# Cherry.net
KiCad netlist of a schematic drawn in Altium Designer
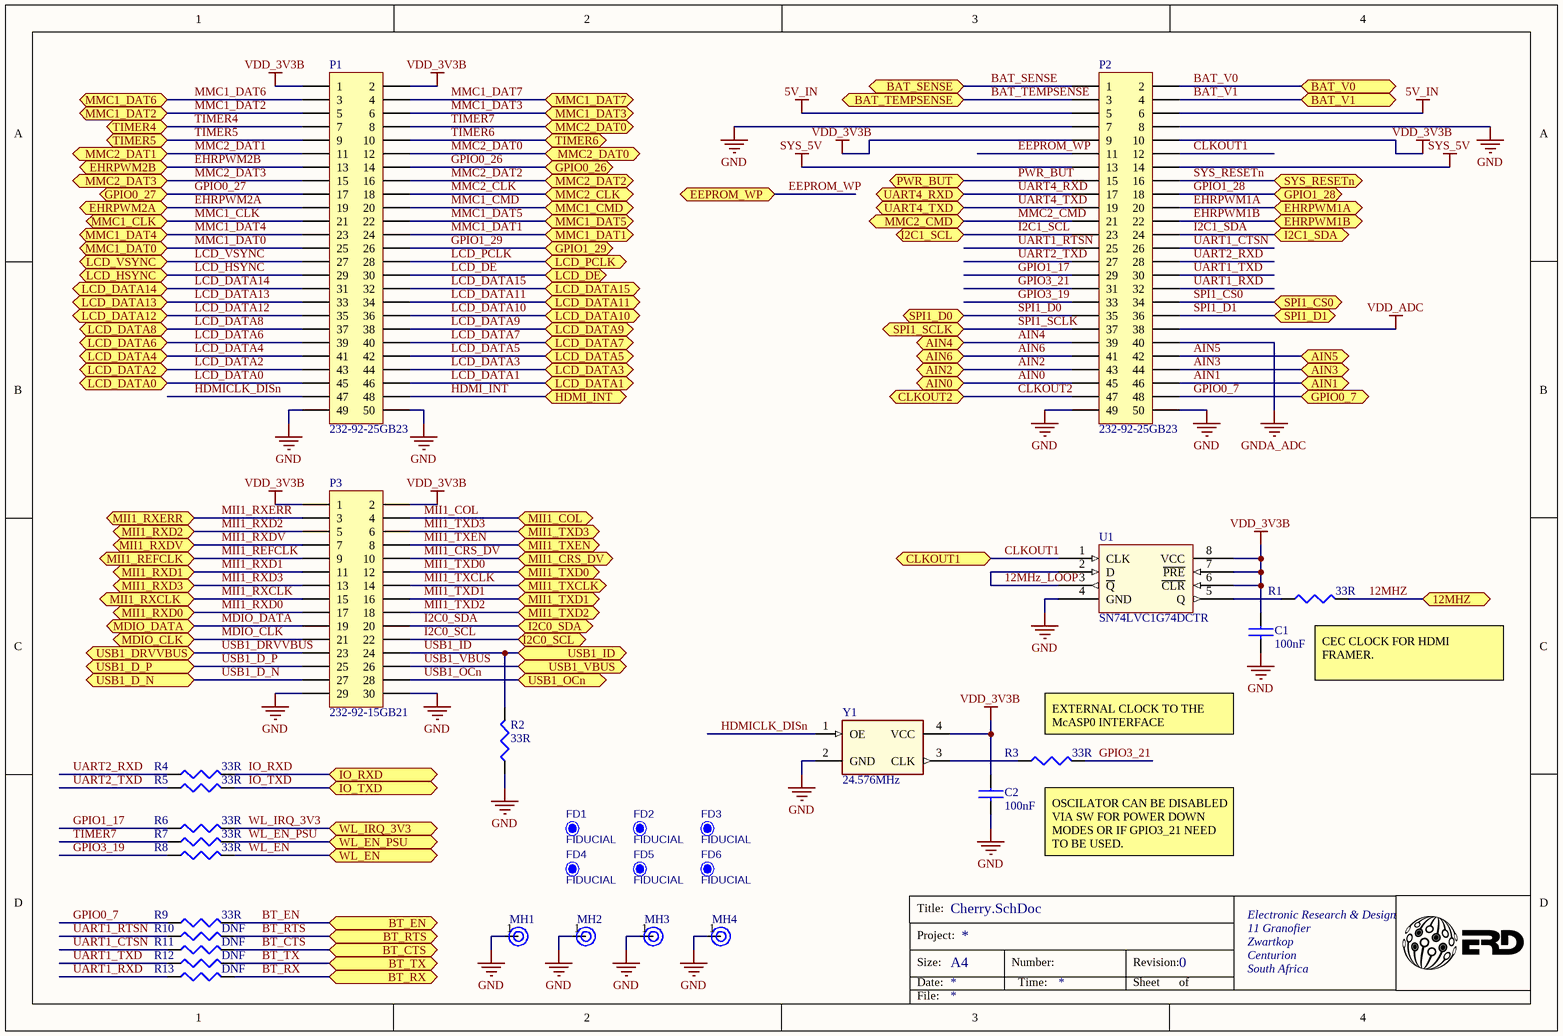
[diagram p0: Cherry.SchDoc]

(export (version "E")
  (design (tool "Eeschema 10.0.6"))
  (components
    (comp (ref "C1")
      (value "100nF")
      (footprint "CC0402")
      (description "CAP CER 0.1UF 50V 10% X7R 0402")
      (fields (field (name "MANUFACTURER") "Murata") (field (name "PARTNUMBER") "GCM155R71H104KE02D"))
      (libsource (lib "ERD TiAm") (part "CAP CER 0.1UF 10V 10% X5R 0402"))
    )
    (comp (ref "C2")
      (value "100nF")
      (footprint "CC0402")
      (description "CAP CER 0.1UF 50V 10% X7R 0402")
      (fields (field (name "MANUFACTURER") "Murata") (field (name "PARTNUMBER") "GCM155R71H104KE02D"))
      (libsource (lib "ERD TiAm") (part "CAP CER 0.1UF 10V 10% X5R 0402"))
    )
    (comp (ref "FD1")
      (value "FIDUCIAL")
      (footprint "FIDUCIAL")
      (description "Fiducial 2mm")
      (libsource (lib "*") (part "FIDUCIAL"))
    )
    (comp (ref "FD2")
      (value "FIDUCIAL")
      (footprint "FIDUCIAL")
      (description "Fiducial 2mm")
      (libsource (lib "*") (part "FIDUCIAL"))
    )
    (comp (ref "FD3")
      (value "FIDUCIAL")
      (footprint "FIDUCIAL")
      (description "Fiducial 2mm")
      (libsource (lib "*") (part "FIDUCIAL"))
    )
    (comp (ref "FD4")
      (value "FIDUCIAL")
      (footprint "FIDUCIAL")
      (description "Fiducial 2mm")
      (libsource (lib "*") (part "FIDUCIAL"))
    )
    (comp (ref "FD5")
      (value "FIDUCIAL")
      (footprint "FIDUCIAL")
      (description "Fiducial 2mm")
      (libsource (lib "*") (part "FIDUCIAL"))
    )
    (comp (ref "FD6")
      (value "FIDUCIAL")
      (footprint "FIDUCIAL")
      (description "Fiducial 2mm")
      (libsource (lib "*") (part "FIDUCIAL"))
    )
    (comp (ref "MH1")
      (value "MH")
      (footprint "MH - M3")
      (description "Mounting Hole")
      (libsource (lib "BCI_rev_0") (part "MountingHole"))
    )
    (comp (ref "MH2")
      (value "MH")
      (footprint "MH - M3")
      (description "Mounting Hole")
      (libsource (lib "BCI_rev_0") (part "MountingHole"))
    )
    (comp (ref "MH3")
      (value "MH")
      (footprint "MH - M3")
      (description "Mounting Hole")
      (libsource (lib "BCI_rev_0") (part "MountingHole"))
    )
    (comp (ref "MH4")
      (value "MH")
      (footprint "MH - M3")
      (description "Mounting Hole")
      (libsource (lib "BCI_rev_0") (part "MountingHole"))
    )
    (comp (ref "P1")
      (value "232-92-25GB23")
      (footprint "232-92-25GB")
      (description "Header, 25-Pin Male, Dual row")
      (fields
        (field (name "MANUFACTURER") "Pinrex")
        (field (name "MANUFACTURER PART NUMBER") "635-92-25GB02")
      )
      (libsource (lib "ERD TiAm") (part "Header 25X2"))
    )
    (comp (ref "P2")
      (value "232-92-25GB23")
      (footprint "232-92-25GB")
      (description "Header, 25-Pin Male, Dual row")
      (fields
        (field (name "MANUFACTURER") "Pinrex")
        (field (name "MANUFACTURER PART NUMBER") "635-92-25GB02")
      )
      (libsource (lib "ERD TiAm") (part "Header 25X2"))
    )
    (comp (ref "P3")
      (value "232-92-15GB21")
      (footprint "232-92-15GB")
      (description "Header, 15-Pin Male, Dual row")
      (fields
        (field (name "MANUFACTURER") "Pinrex")
        (field (name "MANUFACTURER PART NUMBER") "635-92-15GB02")
      )
      (libsource (lib "ERD TiAm") (part "Header 15X2"))
    )
    (comp (ref "R1")
      (value "33R")
      (footprint "RC0402")
      (description "RES, 33 OHM, 1/16W, 1%, 0402")
      (fields (field (name "MANUFACTURER") "Yageo") (field (name "PARTNUMBER") "RC0402FR-0733RL"))
      (libsource (lib "ERD TiAm") (part "RES_10K_1/16W_1%_0402"))
    )
    (comp (ref "R2")
      (value "33R")
      (footprint "RC0402")
      (description "RES, 33 OHM, 1/16W, 1%, 0402")
      (fields (field (name "MANUFACTURER") "Yageo") (field (name "PARTNUMBER") "RC0402FR-0733RL"))
      (libsource (lib "ERD TiAm") (part "RES_10K_1/16W_1%_0402"))
    )
    (comp (ref "R3")
      (value "33R")
      (footprint "RC0402")
      (description "RES, 33 OHM, 1/16W, 1%, 0402")
      (fields (field (name "MANUFACTURER") "Yageo") (field (name "PARTNUMBER") "RC0402FR-0733RL"))
      (libsource (lib "ERD TiAm") (part "RES_10K_1/16W_1%_0402"))
    )
    (comp (ref "R4")
      (value "33R")
      (footprint "RC0402")
      (description "RES, 33 OHM, 1/16W, 1%, 0402")
      (fields (field (name "MANUFACTURER") "Yageo") (field (name "PARTNUMBER") "RC0402FR-0733RL"))
      (libsource (lib "ERD TiAm") (part "RES_10K_1/16W_1%_0402"))
    )
    (comp (ref "R5")
      (value "33R")
      (footprint "RC0402")
      (description "RES, 33 OHM, 1/16W, 1%, 0402")
      (fields (field (name "MANUFACTURER") "Yageo") (field (name "PARTNUMBER") "RC0402FR-0733RL"))
      (libsource (lib "ERD TiAm") (part "RES_10K_1/16W_1%_0402"))
    )
    (comp (ref "R6")
      (value "33R")
      (footprint "RC0402")
      (description "RES, 33 OHM, 1/16W, 1%, 0402")
      (fields (field (name "MANUFACTURER") "Yageo") (field (name "PARTNUMBER") "RC0402FR-0733RL"))
      (libsource (lib "ERD TiAm") (part "RES_10K_1/16W_1%_0402"))
    )
    (comp (ref "R7")
      (value "33R")
      (footprint "RC0402")
      (description "RES, 33 OHM, 1/16W, 1%, 0402")
      (fields (field (name "MANUFACTURER") "Yageo") (field (name "PARTNUMBER") "RC0402FR-0733RL"))
      (libsource (lib "ERD TiAm") (part "RES_10K_1/16W_1%_0402"))
    )
    (comp (ref "R8")
      (value "33R")
      (footprint "RC0402")
      (description "RES, 33 OHM, 1/16W, 1%, 0402")
      (fields (field (name "MANUFACTURER") "Yageo") (field (name "PARTNUMBER") "RC0402FR-0733RL"))
      (libsource (lib "ERD TiAm") (part "RES_10K_1/16W_1%_0402"))
    )
    (comp (ref "R9")
      (value "33R")
      (footprint "RC0402")
      (description "RES, 33 OHM, 1/16W, 1%, 0402")
      (fields (field (name "MANUFACTURER") "Yageo") (field (name "PARTNUMBER") "RC0402FR-0733RL"))
      (libsource (lib "ERD TiAm") (part "RES_10K_1/16W_1%_0402"))
    )
    (comp (ref "R10")
      (value "DNF")
      (footprint "RC0402")
      (description "RES, 33 OHM, 1/16W, 1%, 0402")
      (fields (field (name "MANUFACTURER") "Yageo") (field (name "PARTNUMBER") "RC0402FR-0733RL"))
      (libsource (lib "ERD TiAm") (part "RES_10K_1/16W_1%_0402"))
    )
    (comp (ref "R11")
      (value "DNF")
      (footprint "RC0402")
      (description "RES, 33 OHM, 1/16W, 1%, 0402")
      (fields (field (name "MANUFACTURER") "Yageo") (field (name "PARTNUMBER") "RC0402FR-0733RL"))
      (libsource (lib "ERD TiAm") (part "RES_10K_1/16W_1%_0402"))
    )
    (comp (ref "R12")
      (value "DNF")
      (footprint "RC0402")
      (description "RES, 33 OHM, 1/16W, 1%, 0402")
      (fields (field (name "MANUFACTURER") "Yageo") (field (name "PARTNUMBER") "RC0402FR-0733RL"))
      (libsource (lib "ERD TiAm") (part "RES_10K_1/16W_1%_0402"))
    )
    (comp (ref "R13")
      (value "DNF")
      (footprint "RC0402")
      (description "RES, 33 OHM, 1/16W, 1%, 0402")
      (fields (field (name "MANUFACTURER") "Yageo") (field (name "PARTNUMBER") "RC0402FR-0733RL"))
      (libsource (lib "ERD TiAm") (part "RES_10K_1/16W_1%_0402"))
    )
    (comp (ref "U1")
      (value "SN74LVC1G74DCTR")
      (footprint "SOP8_DCT")
      (description "SINGLE  POSITIVE-EDGE-TRIGGERED  D-TYPE  FLIP-FLOP WITH  CLEAR  AND  PRESET")
      (fields (field (name "MANUFACTURER") "Texas Instruments"))
      (libsource (lib "BEAGLEBONEBLACK_REV A5B") (part "SN74LVC1G74DCTR"))
    )
    (comp (ref "Y1")
      (value "24.576MHz")
      (footprint "OSC_SMD_7x5")
      (fields
        (field (name "MANUFACTURER") "Abracon Corporation")
        (field (name "MANUFACTURER PART NUMBER") "ASDMB-24.576MHZ-LC-T")
      )
      (libsource (lib "BEAGLEBONEBLACK_REV A5B") (part "ASDMB"))
    )
  )
  (nets
    (net (code "1") (name "/12MHZ") (class "Default")
      (node (ref "R1") (pin "2") (pinfunction "2_2") (pintype "passive"))
    )
    (net (code "2") (name "/12MHz_LOOP") (class "Default")
      (node (ref "U1") (pin "2") (pinfunction "D_2") (pintype "input"))
      (node (ref "U1") (pin "3") (pinfunction "~{Q}_3") (pintype "output"))
    )
    (net (code "3") (name "/AIN0") (class "Default")
      (node (ref "P2") (pin "45") (pinfunction "45_45") (pintype "passive"))
    )
    (net (code "4") (name "/AIN1") (class "Default")
      (node (ref "P2") (pin "46") (pinfunction "46_46") (pintype "passive"))
    )
    (net (code "5") (name "/AIN2") (class "Default")
      (node (ref "P2") (pin "43") (pinfunction "43_43") (pintype "passive"))
    )
    (net (code "6") (name "/AIN3") (class "Default")
      (node (ref "P2") (pin "44") (pinfunction "44_44") (pintype "passive"))
    )
    (net (code "7") (name "/AIN4") (class "Default")
      (node (ref "P2") (pin "39") (pinfunction "39_39") (pintype "passive"))
    )
    (net (code "8") (name "/AIN5") (class "Default")
      (node (ref "P2") (pin "42") (pinfunction "42_42") (pintype "passive"))
    )
    (net (code "9") (name "/AIN6") (class "Default")
      (node (ref "P2") (pin "41") (pinfunction "41_41") (pintype "passive"))
    )
    (net (code "10") (name "/BAT_SENSE") (class "Default")
      (node (ref "P2") (pin "1") (pinfunction "1_1") (pintype "passive"))
    )
    (net (code "11") (name "/BAT_TEMPSENSE") (class "Default")
      (node (ref "P2") (pin "3") (pinfunction "3_3") (pintype "passive"))
    )
    (net (code "12") (name "/BAT_V0") (class "Default")
      (node (ref "P2") (pin "2") (pinfunction "2_2") (pintype "passive"))
    )
    (net (code "13") (name "/BAT_V1") (class "Default")
      (node (ref "P2") (pin "4") (pinfunction "4_4") (pintype "passive"))
    )
    (net (code "14") (name "/BT_CTS") (class "Default")
      (node (ref "R11") (pin "2") (pinfunction "2_2") (pintype "passive"))
    )
    (net (code "15") (name "/BT_EN") (class "Default")
      (node (ref "R9") (pin "2") (pinfunction "2_2") (pintype "passive"))
    )
    (net (code "16") (name "/BT_RTS") (class "Default")
      (node (ref "R10") (pin "2") (pinfunction "2_2") (pintype "passive"))
    )
    (net (code "17") (name "/BT_RX") (class "Default")
      (node (ref "R13") (pin "2") (pinfunction "2_2") (pintype "passive"))
    )
    (net (code "18") (name "/BT_TX") (class "Default")
      (node (ref "R12") (pin "2") (pinfunction "2_2") (pintype "passive"))
    )
    (net (code "19") (name "/CLKOUT1") (class "Default")
      (node (ref "P2") (pin "12") (pinfunction "12_12") (pintype "passive"))
      (node (ref "U1") (pin "1") (pinfunction "CLK_1") (pintype "input"))
    )
    (net (code "20") (name "/CLKOUT2") (class "Default")
      (node (ref "P2") (pin "47") (pinfunction "47_47") (pintype "passive"))
    )
    (net (code "21") (name "/EEPROM_WP") (class "Default")
      (node (ref "P2") (pin "11") (pinfunction "11_11") (pintype "passive"))
    )
    (net (code "22") (name "/EHRPWM1A") (class "Default")
      (node (ref "P2") (pin "20") (pinfunction "20_20") (pintype "passive"))
    )
    (net (code "23") (name "/EHRPWM1B") (class "Default")
      (node (ref "P2") (pin "22") (pinfunction "22_22") (pintype "passive"))
    )
    (net (code "24") (name "/EHRPWM2A") (class "Default")
      (node (ref "P1") (pin "19") (pinfunction "19_19") (pintype "passive"))
    )
    (net (code "25") (name "/EHRPWM2B") (class "Default")
      (node (ref "P1") (pin "13") (pinfunction "13_13") (pintype "passive"))
    )
    (net (code "26") (name "/GPIO0_7") (class "Default")
      (node (ref "P2") (pin "48") (pinfunction "48_48") (pintype "passive"))
      (node (ref "R9") (pin "1") (pinfunction "1_1") (pintype "passive"))
    )
    (net (code "27") (name "/GPIO0_26") (class "Default")
      (node (ref "P1") (pin "14") (pinfunction "14_14") (pintype "passive"))
    )
    (net (code "28") (name "/GPIO0_27") (class "Default")
      (node (ref "P1") (pin "17") (pinfunction "17_17") (pintype "passive"))
    )
    (net (code "29") (name "/GPIO1_17") (class "Default")
      (node (ref "P2") (pin "29") (pinfunction "29_29") (pintype "passive"))
      (node (ref "R6") (pin "1") (pinfunction "1_1") (pintype "passive"))
    )
    (net (code "30") (name "/GPIO1_28") (class "Default")
      (node (ref "P2") (pin "18") (pinfunction "18_18") (pintype "passive"))
    )
    (net (code "31") (name "/GPIO1_29") (class "Default")
      (node (ref "P1") (pin "26") (pinfunction "26_26") (pintype "passive"))
    )
    (net (code "32") (name "/GPIO3_19") (class "Default")
      (node (ref "P2") (pin "33") (pinfunction "33_33") (pintype "passive"))
      (node (ref "R8") (pin "1") (pinfunction "1_1") (pintype "passive"))
    )
    (net (code "33") (name "/GPIO3_21") (class "Default")
      (node (ref "P2") (pin "31") (pinfunction "31_31") (pintype "passive"))
      (node (ref "R3") (pin "2") (pinfunction "2_2") (pintype "passive"))
    )
    (net (code "34") (name "/HDMICLK_DISn") (class "Default")
      (node (ref "P1") (pin "47") (pinfunction "47_47") (pintype "passive"))
      (node (ref "Y1") (pin "1") (pinfunction "OE_1") (pintype "input"))
    )
    (net (code "35") (name "/HDMI_INT") (class "Default")
      (node (ref "P1") (pin "48") (pinfunction "48_48") (pintype "passive"))
    )
    (net (code "36") (name "/I2C0_SCL") (class "Default")
      (node (ref "P3") (pin "22") (pinfunction "22_22") (pintype "passive"))
    )
    (net (code "37") (name "/I2C0_SDA") (class "Default")
      (node (ref "P3") (pin "20") (pinfunction "20_20") (pintype "passive"))
    )
    (net (code "38") (name "/I2C1_SCL") (class "Default")
      (node (ref "P2") (pin "23") (pinfunction "23_23") (pintype "passive"))
    )
    (net (code "39") (name "/I2C1_SDA") (class "Default")
      (node (ref "P2") (pin "24") (pinfunction "24_24") (pintype "passive"))
    )
    (net (code "40") (name "/IO_RXD") (class "Default")
      (node (ref "R4") (pin "2") (pinfunction "2_2") (pintype "passive"))
    )
    (net (code "41") (name "/IO_TXD") (class "Default")
      (node (ref "R5") (pin "2") (pinfunction "2_2") (pintype "passive"))
    )
    (net (code "42") (name "/LCD_DATA0") (class "Default")
      (node (ref "P1") (pin "45") (pinfunction "45_45") (pintype "passive"))
    )
    (net (code "43") (name "/LCD_DATA1") (class "Default")
      (node (ref "P1") (pin "46") (pinfunction "46_46") (pintype "passive"))
    )
    (net (code "44") (name "/LCD_DATA2") (class "Default")
      (node (ref "P1") (pin "43") (pinfunction "43_43") (pintype "passive"))
    )
    (net (code "45") (name "/LCD_DATA3") (class "Default")
      (node (ref "P1") (pin "44") (pinfunction "44_44") (pintype "passive"))
    )
    (net (code "46") (name "/LCD_DATA4") (class "Default")
      (node (ref "P1") (pin "41") (pinfunction "41_41") (pintype "passive"))
    )
    (net (code "47") (name "/LCD_DATA5") (class "Default")
      (node (ref "P1") (pin "42") (pinfunction "42_42") (pintype "passive"))
    )
    (net (code "48") (name "/LCD_DATA6") (class "Default")
      (node (ref "P1") (pin "39") (pinfunction "39_39") (pintype "passive"))
    )
    (net (code "49") (name "/LCD_DATA7") (class "Default")
      (node (ref "P1") (pin "40") (pinfunction "40_40") (pintype "passive"))
    )
    (net (code "50") (name "/LCD_DATA8") (class "Default")
      (node (ref "P1") (pin "37") (pinfunction "37_37") (pintype "passive"))
    )
    (net (code "51") (name "/LCD_DATA9") (class "Default")
      (node (ref "P1") (pin "38") (pinfunction "38_38") (pintype "passive"))
    )
    (net (code "52") (name "/LCD_DATA10") (class "Default")
      (node (ref "P1") (pin "36") (pinfunction "36_36") (pintype "passive"))
    )
    (net (code "53") (name "/LCD_DATA11") (class "Default")
      (node (ref "P1") (pin "34") (pinfunction "34_34") (pintype "passive"))
    )
    (net (code "54") (name "/LCD_DATA12") (class "Default")
      (node (ref "P1") (pin "35") (pinfunction "35_35") (pintype "passive"))
    )
    (net (code "55") (name "/LCD_DATA13") (class "Default")
      (node (ref "P1") (pin "33") (pinfunction "33_33") (pintype "passive"))
    )
    (net (code "56") (name "/LCD_DATA14") (class "Default")
      (node (ref "P1") (pin "31") (pinfunction "31_31") (pintype "passive"))
    )
    (net (code "57") (name "/LCD_DATA15") (class "Default")
      (node (ref "P1") (pin "32") (pinfunction "32_32") (pintype "passive"))
    )
    (net (code "58") (name "/LCD_DE") (class "Default")
      (node (ref "P1") (pin "30") (pinfunction "30_30") (pintype "passive"))
    )
    (net (code "59") (name "/LCD_HSYNC") (class "Default")
      (node (ref "P1") (pin "29") (pinfunction "29_29") (pintype "passive"))
    )
    (net (code "60") (name "/LCD_PCLK") (class "Default")
      (node (ref "P1") (pin "28") (pinfunction "28_28") (pintype "passive"))
    )
    (net (code "61") (name "/LCD_VSYNC") (class "Default")
      (node (ref "P1") (pin "27") (pinfunction "27_27") (pintype "passive"))
    )
    (net (code "62") (name "/MDIO_CLK") (class "Default")
      (node (ref "P3") (pin "21") (pinfunction "21_21") (pintype "passive"))
    )
    (net (code "63") (name "/MDIO_DATA") (class "Default")
      (node (ref "P3") (pin "19") (pinfunction "19_19") (pintype "passive"))
    )
    (net (code "64") (name "/MII1_COL") (class "Default")
      (node (ref "P3") (pin "4") (pinfunction "4_4") (pintype "passive"))
    )
    (net (code "65") (name "/MII1_CRS_DV") (class "Default")
      (node (ref "P3") (pin "10") (pinfunction "10_10") (pintype "passive"))
    )
    (net (code "66") (name "/MII1_REFCLK") (class "Default")
      (node (ref "P3") (pin "9") (pinfunction "9_9") (pintype "passive"))
    )
    (net (code "67") (name "/MII1_RXCLK") (class "Default")
      (node (ref "P3") (pin "15") (pinfunction "15_15") (pintype "passive"))
    )
    (net (code "68") (name "/MII1_RXD0") (class "Default")
      (node (ref "P3") (pin "17") (pinfunction "17_17") (pintype "passive"))
    )
    (net (code "69") (name "/MII1_RXD1") (class "Default")
      (node (ref "P3") (pin "11") (pinfunction "11_11") (pintype "passive"))
    )
    (net (code "70") (name "/MII1_RXD2") (class "Default")
      (node (ref "P3") (pin "5") (pinfunction "5_5") (pintype "passive"))
    )
    (net (code "71") (name "/MII1_RXD3") (class "Default")
      (node (ref "P3") (pin "13") (pinfunction "13_13") (pintype "passive"))
    )
    (net (code "72") (name "/MII1_RXDV") (class "Default")
      (node (ref "P3") (pin "7") (pinfunction "7_7") (pintype "passive"))
    )
    (net (code "73") (name "/MII1_RXERR") (class "Default")
      (node (ref "P3") (pin "3") (pinfunction "3_3") (pintype "passive"))
    )
    (net (code "74") (name "/MII1_TXCLK") (class "Default")
      (node (ref "P3") (pin "14") (pinfunction "14_14") (pintype "passive"))
    )
    (net (code "75") (name "/MII1_TXD0") (class "Default")
      (node (ref "P3") (pin "12") (pinfunction "12_12") (pintype "passive"))
    )
    (net (code "76") (name "/MII1_TXD1") (class "Default")
      (node (ref "P3") (pin "16") (pinfunction "16_16") (pintype "passive"))
    )
    (net (code "77") (name "/MII1_TXD2") (class "Default")
      (node (ref "P3") (pin "18") (pinfunction "18_18") (pintype "passive"))
    )
    (net (code "78") (name "/MII1_TXD3") (class "Default")
      (node (ref "P3") (pin "6") (pinfunction "6_6") (pintype "passive"))
    )
    (net (code "79") (name "/MII1_TXEN") (class "Default")
      (node (ref "P3") (pin "8") (pinfunction "8_8") (pintype "passive"))
    )
    (net (code "80") (name "/MMC1_CLK") (class "Default")
      (node (ref "P1") (pin "21") (pinfunction "21_21") (pintype "passive"))
    )
    (net (code "81") (name "/MMC1_CMD") (class "Default")
      (node (ref "P1") (pin "20") (pinfunction "20_20") (pintype "passive"))
    )
    (net (code "82") (name "/MMC1_DAT0") (class "Default")
      (node (ref "P1") (pin "25") (pinfunction "25_25") (pintype "passive"))
    )
    (net (code "83") (name "/MMC1_DAT1") (class "Default")
      (node (ref "P1") (pin "24") (pinfunction "24_24") (pintype "passive"))
    )
    (net (code "84") (name "/MMC1_DAT2") (class "Default")
      (node (ref "P1") (pin "5") (pinfunction "5_5") (pintype "passive"))
    )
    (net (code "85") (name "/MMC1_DAT3") (class "Default")
      (node (ref "P1") (pin "6") (pinfunction "6_6") (pintype "passive"))
    )
    (net (code "86") (name "/MMC1_DAT4") (class "Default")
      (node (ref "P1") (pin "23") (pinfunction "23_23") (pintype "passive"))
    )
    (net (code "87") (name "/MMC1_DAT5") (class "Default")
      (node (ref "P1") (pin "22") (pinfunction "22_22") (pintype "passive"))
    )
    (net (code "88") (name "/MMC1_DAT6") (class "Default")
      (node (ref "P1") (pin "3") (pinfunction "3_3") (pintype "passive"))
    )
    (net (code "89") (name "/MMC1_DAT7") (class "Default")
      (node (ref "P1") (pin "4") (pinfunction "4_4") (pintype "passive"))
    )
    (net (code "90") (name "/MMC2_CLK") (class "Default")
      (node (ref "P1") (pin "18") (pinfunction "18_18") (pintype "passive"))
    )
    (net (code "91") (name "/MMC2_CMD") (class "Default")
      (node (ref "P2") (pin "21") (pinfunction "21_21") (pintype "passive"))
    )
    (net (code "92") (name "/MMC2_DAT0") (class "Default")
      (node (ref "P1") (pin "12") (pinfunction "12_12") (pintype "passive"))
      (node (ref "P1") (pin "8") (pinfunction "8_8") (pintype "passive"))
      (node (ref "R7") (pin "1") (pinfunction "1_1") (pintype "passive"))
    )
    (net (code "93") (name "/MMC2_DAT1") (class "Default")
      (node (ref "P1") (pin "11") (pinfunction "11_11") (pintype "passive"))
    )
    (net (code "94") (name "/MMC2_DAT2") (class "Default")
      (node (ref "P1") (pin "16") (pinfunction "16_16") (pintype "passive"))
    )
    (net (code "95") (name "/MMC2_DAT3") (class "Default")
      (node (ref "P1") (pin "15") (pinfunction "15_15") (pintype "passive"))
    )
    (net (code "96") (name "/PWR_BUT") (class "Default")
      (node (ref "P2") (pin "15") (pinfunction "15_15") (pintype "passive"))
    )
    (net (code "97") (name "/SPI1_CS0") (class "Default")
      (node (ref "P2") (pin "34") (pinfunction "34_34") (pintype "passive"))
    )
    (net (code "98") (name "/SPI1_D0") (class "Default")
      (node (ref "P2") (pin "35") (pinfunction "35_35") (pintype "passive"))
    )
    (net (code "99") (name "/SPI1_D1") (class "Default")
      (node (ref "P2") (pin "36") (pinfunction "36_36") (pintype "passive"))
    )
    (net (code "100") (name "/SPI1_SCLK") (class "Default")
      (node (ref "P2") (pin "37") (pinfunction "37_37") (pintype "passive"))
    )
    (net (code "101") (name "/SYS_RESETn") (class "Default")
      (node (ref "P2") (pin "16") (pinfunction "16_16") (pintype "passive"))
    )
    (net (code "102") (name "/TIMER4") (class "Default")
      (node (ref "P1") (pin "7") (pinfunction "7_7") (pintype "passive"))
    )
    (net (code "103") (name "/TIMER5") (class "Default")
      (node (ref "P1") (pin "9") (pinfunction "9_9") (pintype "passive"))
    )
    (net (code "104") (name "/TIMER6") (class "Default")
      (node (ref "P1") (pin "10") (pinfunction "10_10") (pintype "passive"))
    )
    (net (code "105") (name "/UART1_CTSN") (class "Default")
      (node (ref "P2") (pin "26") (pinfunction "26_26") (pintype "passive"))
      (node (ref "R11") (pin "1") (pinfunction "1_1") (pintype "passive"))
    )
    (net (code "106") (name "/UART1_RTSN") (class "Default")
      (node (ref "P2") (pin "25") (pinfunction "25_25") (pintype "passive"))
      (node (ref "R10") (pin "1") (pinfunction "1_1") (pintype "passive"))
    )
    (net (code "107") (name "/UART1_RXD") (class "Default")
      (node (ref "P2") (pin "32") (pinfunction "32_32") (pintype "passive"))
      (node (ref "R13") (pin "1") (pinfunction "1_1") (pintype "passive"))
    )
    (net (code "108") (name "/UART1_TXD") (class "Default")
      (node (ref "P2") (pin "30") (pinfunction "30_30") (pintype "passive"))
      (node (ref "R12") (pin "1") (pinfunction "1_1") (pintype "passive"))
    )
    (net (code "109") (name "/UART2_RXD") (class "Default")
      (node (ref "P2") (pin "28") (pinfunction "28_28") (pintype "passive"))
      (node (ref "R4") (pin "1") (pinfunction "1_1") (pintype "passive"))
    )
    (net (code "110") (name "/UART2_TXD") (class "Default")
      (node (ref "P2") (pin "27") (pinfunction "27_27") (pintype "passive"))
      (node (ref "R5") (pin "1") (pinfunction "1_1") (pintype "passive"))
    )
    (net (code "111") (name "/UART4_RXD") (class "Default")
      (node (ref "P2") (pin "17") (pinfunction "17_17") (pintype "passive"))
    )
    (net (code "112") (name "/UART4_TXD") (class "Default")
      (node (ref "P2") (pin "19") (pinfunction "19_19") (pintype "passive"))
    )
    (net (code "113") (name "/USB1_DRVVBUS") (class "Default")
      (node (ref "P3") (pin "23") (pinfunction "23_23") (pintype "passive"))
    )
    (net (code "114") (name "/USB1_D_N") (class "Default")
      (node (ref "P3") (pin "27") (pinfunction "27_27") (pintype "passive"))
    )
    (net (code "115") (name "/USB1_D_P") (class "Default")
      (node (ref "P3") (pin "25") (pinfunction "25_25") (pintype "passive"))
    )
    (net (code "116") (name "/USB1_ID") (class "Default")
      (node (ref "P3") (pin "24") (pinfunction "24_24") (pintype "passive"))
      (node (ref "R2") (pin "2") (pinfunction "2_2") (pintype "passive"))
    )
    (net (code "117") (name "/USB1_OCn") (class "Default")
      (node (ref "P3") (pin "28") (pinfunction "28_28") (pintype "passive"))
    )
    (net (code "118") (name "/USB1_VBUS") (class "Default")
      (node (ref "P3") (pin "26") (pinfunction "26_26") (pintype "passive"))
    )
    (net (code "119") (name "/WL_EN") (class "Default")
      (node (ref "R8") (pin "2") (pinfunction "2_2") (pintype "passive"))
    )
    (net (code "120") (name "/WL_EN_PSU") (class "Default")
      (node (ref "R7") (pin "2") (pinfunction "2_2") (pintype "passive"))
    )
    (net (code "121") (name "/WL_IRQ_3V3") (class "Default")
      (node (ref "R6") (pin "2") (pinfunction "2_2") (pintype "passive"))
    )
    (net (code "122") (name "5V_IN") (class "Default")
      (node (ref "P2") (pin "5") (pinfunction "5_5") (pintype "passive"))
      (node (ref "P2") (pin "6") (pinfunction "6_6") (pintype "passive"))
    )
    (net (code "123") (name "GND") (class "Default")
      (node (ref "C1") (pin "2") (pinfunction "2_2") (pintype "passive"))
      (node (ref "C2") (pin "2") (pinfunction "2_2") (pintype "passive"))
      (node (ref "MH1") (pin "1") (pinfunction "1_1") (pintype "passive"))
      (node (ref "MH2") (pin "1") (pinfunction "1_1") (pintype "passive"))
      (node (ref "MH3") (pin "1") (pinfunction "1_1") (pintype "passive"))
      (node (ref "MH4") (pin "1") (pinfunction "1_1") (pintype "passive"))
      (node (ref "P1") (pin "49") (pinfunction "49_49") (pintype "passive"))
      (node (ref "P1") (pin "50") (pinfunction "50_50") (pintype "passive"))
      (node (ref "P2") (pin "49") (pinfunction "49_49") (pintype "passive"))
      (node (ref "P2") (pin "50") (pinfunction "50_50") (pintype "passive"))
      (node (ref "P2") (pin "7") (pinfunction "7_7") (pintype "passive"))
      (node (ref "P2") (pin "8") (pinfunction "8_8") (pintype "passive"))
      (node (ref "P3") (pin "29") (pinfunction "29_29") (pintype "passive"))
      (node (ref "P3") (pin "30") (pinfunction "30_30") (pintype "passive"))
      (node (ref "R2") (pin "1") (pinfunction "1_1") (pintype "passive"))
      (node (ref "U1") (pin "4") (pinfunction "GND_4") (pintype "power_in"))
      (node (ref "Y1") (pin "2") (pinfunction "GND_2") (pintype "power_in"))
    )
    (net (code "124") (name "GNDA_ADC") (class "Default")
      (node (ref "P2") (pin "40") (pinfunction "40_40") (pintype "passive"))
    )
    (net (code "125") (name "Net-(U1-Q)") (class "Default")
      (node (ref "R1") (pin "1") (pinfunction "1_1") (pintype "passive"))
      (node (ref "U1") (pin "5") (pinfunction "Q_5") (pintype "output"))
    )
    (net (code "126") (name "Net-(Y1-CLK)") (class "Default")
      (node (ref "R3") (pin "1") (pinfunction "1_1") (pintype "passive"))
      (node (ref "Y1") (pin "3") (pinfunction "CLK_3") (pintype "output"))
    )
    (net (code "127") (name "SYS_5V") (class "Default")
      (node (ref "P2") (pin "13") (pinfunction "13_13") (pintype "passive"))
      (node (ref "P2") (pin "14") (pinfunction "14_14") (pintype "passive"))
    )
    (net (code "128") (name "VDD_3V3B") (class "Default")
      (node (ref "C1") (pin "1") (pinfunction "1_1") (pintype "passive"))
      (node (ref "C2") (pin "1") (pinfunction "1_1") (pintype "passive"))
      (node (ref "P1") (pin "1") (pinfunction "1_1") (pintype "passive"))
      (node (ref "P1") (pin "2") (pinfunction "2_2") (pintype "passive"))
      (node (ref "P2") (pin "10") (pinfunction "10_10") (pintype "passive"))
      (node (ref "P2") (pin "9") (pinfunction "9_9") (pintype "passive"))
      (node (ref "P3") (pin "1") (pinfunction "1_1") (pintype "passive"))
      (node (ref "P3") (pin "2") (pinfunction "2_2") (pintype "passive"))
      (node (ref "U1") (pin "6") (pinfunction "~{CLR}_6") (pintype "input"))
      (node (ref "U1") (pin "7") (pinfunction "~{PRE}_7") (pintype "input"))
      (node (ref "U1") (pin "8") (pinfunction "VCC_8") (pintype "power_in"))
      (node (ref "Y1") (pin "4") (pinfunction "VCC_4") (pintype "power_in"))
    )
    (net (code "129") (name "VDD_ADC") (class "Default")
      (node (ref "P2") (pin "38") (pinfunction "38_38") (pintype "passive"))
    )
  )
)
